# GARY_Backplane_PowerSupply.net
KiCad netlist of a schematic drawn in Altium Designer
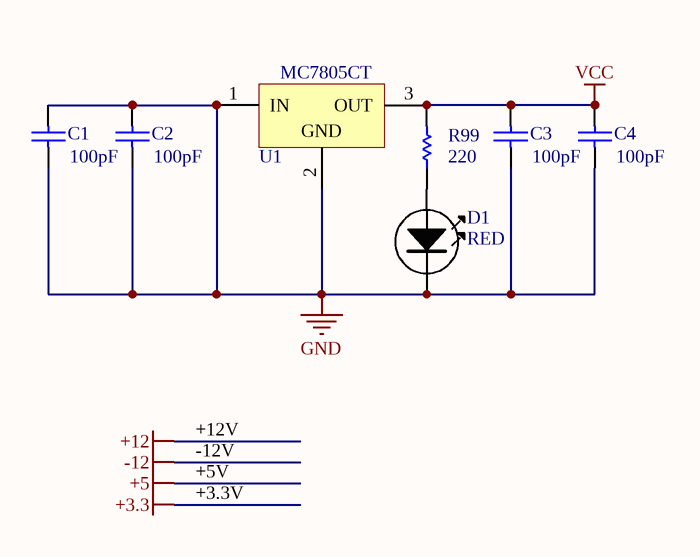
[diagram p0: GARY_Backplane_PowerSupply.SchDoc]

(export (version "E")
  (design (tool "Eeschema 10.0.6"))
  (components
    (comp (ref "C1")
      (value "100pF")
      (footprint "RAD-0.3")
      (description "Capacitor")
      (fields (field (name "Comment") "Cap") (field (name "PUBLISHER") "Altium Limited"))
      (libsource (lib "Miscellaneous Devices") (part "Cap"))
    )
    (comp (ref "C2")
      (value "100pF")
      (footprint "RAD-0.3")
      (description "Capacitor")
      (fields (field (name "Comment") "Cap") (field (name "PUBLISHER") "Altium Limited"))
      (libsource (lib "Miscellaneous Devices") (part "Cap"))
    )
    (comp (ref "C3")
      (value "100pF")
      (footprint "RAD-0.3")
      (description "Capacitor")
      (fields (field (name "Comment") "Cap") (field (name "PUBLISHER") "Altium Limited"))
      (libsource (lib "Miscellaneous Devices") (part "Cap"))
    )
    (comp (ref "C4")
      (value "100pF")
      (footprint "RAD-0.3")
      (description "Capacitor")
      (fields (field (name "Comment") "Cap") (field (name "PUBLISHER") "Altium Limited"))
      (libsource (lib "Miscellaneous Devices") (part "Cap"))
    )
    (comp (ref "D1")
      (value "RED")
      (footprint "LED-5MM-RED")
      (description "LED-RED-5MM")
      (libsource (lib "vh_altium_library") (part "LED-RED-5MM"))
    )
    (comp (ref "R99")
      (value "220")
      (footprint "AXIAL-0.3")
      (description "Resistor")
      (fields (field (name "PUBLISHER") "Altium Limited"))
      (libsource (lib "Miscellaneous Devices") (part "Res1"))
    )
    (comp (ref "U1")
      (value "MC7805CT")
      (footprint "221A-06")
      (description "Three-Terminal Positive Voltage Regulator")
      (fields (field (name "PUBLISHER") "Altium Limited"))
      (libsource (lib "ON Semi Power Mgt Voltage Regulator") (part "MC7805CT"))
    )
  )
  (nets
    (net (code "5") (name "GND") (class "Default")
      (node (ref "C1") (pin "1") (pinfunction "1_1") (pintype "passive"))
      (node (ref "C1") (pin "2") (pinfunction "2_2") (pintype "passive"))
      (node (ref "C2") (pin "1") (pinfunction "1_1") (pintype "passive"))
      (node (ref "C2") (pin "2") (pinfunction "2_2") (pintype "passive"))
      (node (ref "C3") (pin "1") (pinfunction "1_1") (pintype "passive"))
      (node (ref "C4") (pin "1") (pinfunction "1_1") (pintype "passive"))
      (node (ref "D1") (pin "K") (pintype "passive"))
      (node (ref "U1") (pin "1") (pinfunction "IN_1") (pintype "power_in"))
      (node (ref "U1") (pin "2") (pinfunction "GND_2") (pintype "power_in"))
    )
    (net (code "6") (name "Net-(D1-PadA)") (class "Default")
      (node (ref "D1") (pin "A") (pintype "passive"))
      (node (ref "R99") (pin "1") (pinfunction "1_1") (pintype "passive"))
    )
    (net (code "7") (name "VCC") (class "Default")
      (node (ref "C3") (pin "2") (pinfunction "2_2") (pintype "passive"))
      (node (ref "C4") (pin "2") (pinfunction "2_2") (pintype "passive"))
      (node (ref "R99") (pin "2") (pinfunction "2_2") (pintype "passive"))
      (node (ref "U1") (pin "3") (pinfunction "OUT_3") (pintype "power_in"))
    )
  )
)
